# Peripherial.net
KiCad netlist of a schematic drawn in Altium Designer
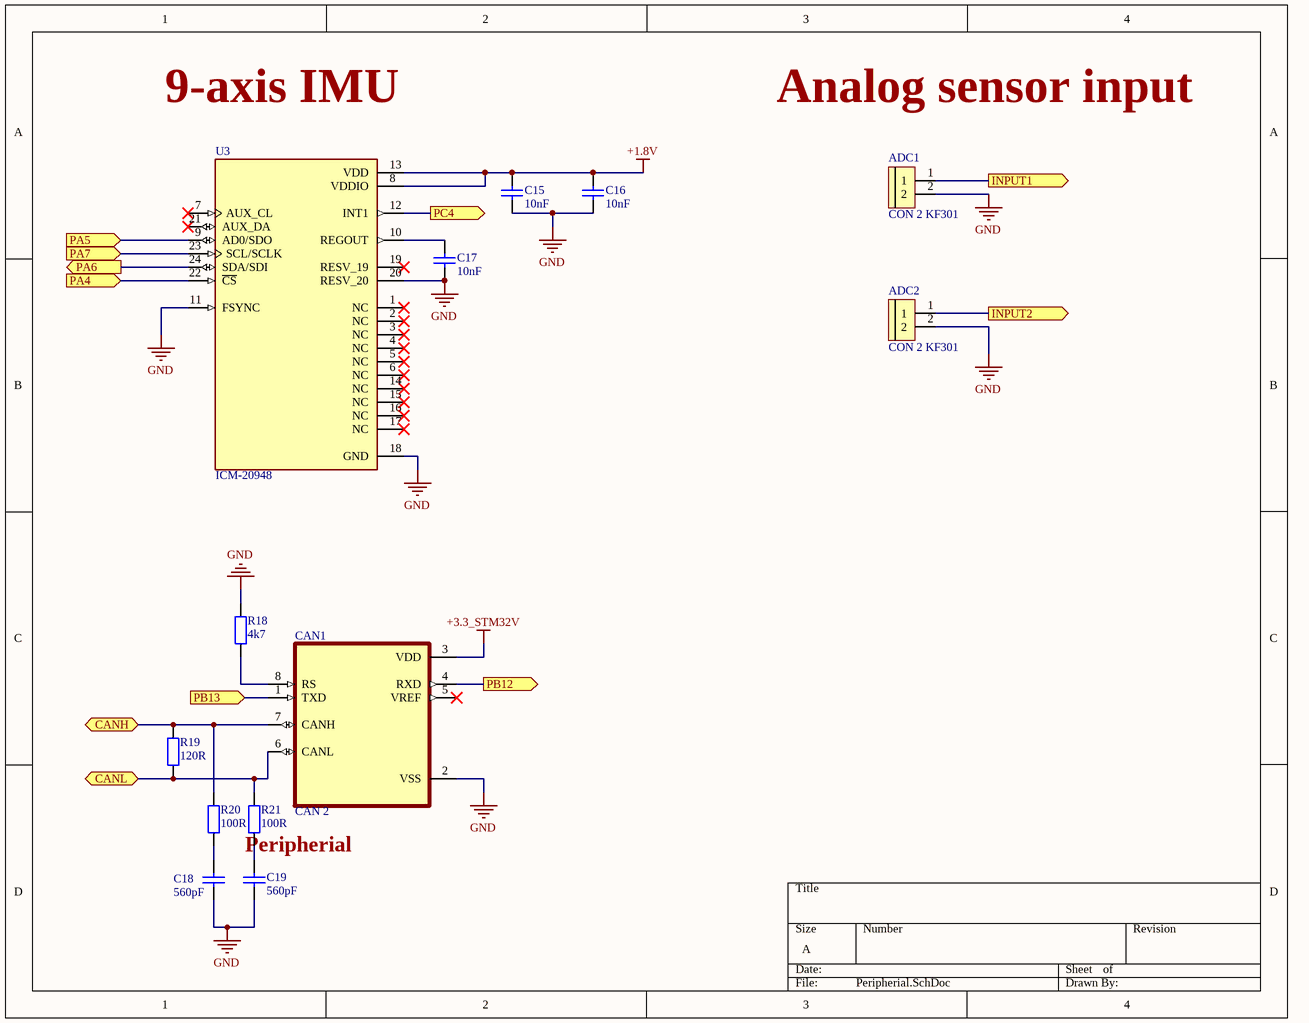
[diagram p0: Peripherial.SchDoc]

(export (version "E")
  (design (tool "Eeschema 10.0.6"))
  (components
    (comp (ref "ADC1")
      (value "CON 2 KF301")
      (footprint "Con 2 KF301 5.08")
      (description "Cắm")
      (libsource (lib "Altium_Lib_by_KhueNguyenCreator") (part "CON 2 KF301"))
    )
    (comp (ref "ADC2")
      (value "CON 2 KF301")
      (footprint "Con 2 KF301 5.08")
      (description "Cắm")
      (libsource (lib "Altium_Lib_by_KhueNguyenCreator") (part "CON 2 KF301"))
    )
    (comp (ref "C15")
      (value "10nF")
      (footprint "tu 0805")
      (description "Dán")
      (libsource (lib "Altium_Lib_by_KhueNguyenCreator") (part "Tu 0805 106 16V 10%"))
    )
    (comp (ref "C16")
      (value "10nF")
      (footprint "tu 0805")
      (description "Dán")
      (libsource (lib "Altium_Lib_by_KhueNguyenCreator") (part "Tu 0805 106 16V 10%"))
    )
    (comp (ref "C17")
      (value "10nF")
      (footprint "tu 0805")
      (description "Dán")
      (libsource (lib "Altium_Lib_by_KhueNguyenCreator") (part "Tu 0805 106 16V 10%"))
    )
    (comp (ref "C18")
      (value "560pF")
      (footprint "tu 0805")
      (description "Dán")
      (libsource (lib "Altium_Lib_by_KhueNguyenCreator") (part "Tu 0805 106 16V 10%"))
    )
    (comp (ref "C19")
      (value "560pF")
      (footprint "tu 0805")
      (description "Dán")
      (libsource (lib "Altium_Lib_by_KhueNguyenCreator") (part "Tu 0805 106 16V 10%"))
    )
    (comp (ref "CAN1")
      (value "CAN 2")
      (footprint "MCP2551-I_SN:SOIC127P599X175-8N")
      (fields
        (field (name "MF") "{'manufacturer': u'Microchip Technology'}")
        (field (name "MP") "MCP2551-I/SN")
      )
      (libsource (lib "*") (part "MCP2551-I/SN"))
    )
    (comp (ref "R18")
      (value "4k7")
      (footprint "tro smd 0805")
      (description "Dán")
      (libsource (lib "Altium_Lib_by_KhueNguyenCreator") (part "Tro 0805 1% 10k"))
    )
    (comp (ref "R19")
      (value "120R")
      (footprint "tro smd 0805")
      (description "Dán")
      (libsource (lib "Altium_Lib_by_KhueNguyenCreator") (part "Tro 0805 1% 10k"))
    )
    (comp (ref "R20")
      (value "100R")
      (footprint "tro smd 0805")
      (description "Dán")
      (libsource (lib "Altium_Lib_by_KhueNguyenCreator") (part "Tro 0805 1% 10k"))
    )
    (comp (ref "R21")
      (value "100R")
      (footprint "tro smd 0805")
      (description "Dán")
      (libsource (lib "Altium_Lib_by_KhueNguyenCreator") (part "Tro 0805 1% 10k"))
    )
    (comp (ref "U3")
      (value "ICM-20948")
      (footprint "QFN40P300X300X105-24N")
      (description "Accelerometer, Gyroscope, Magnetometer, 9 Axis Sensor IÂ²C, SPI Output")
      (libsource (lib "ICM-20948") (part "ICM-20948"))
    )
  )
  (nets
    (net (code "1") (name "+1.8V") (class "Default")
      (node (ref "C15") (pin "1") (pinfunction "1_1") (pintype "passive"))
      (node (ref "C16") (pin "1") (pinfunction "1_1") (pintype "passive"))
      (node (ref "U3") (pin "13") (pinfunction "VDD_13") (pintype "power_in"))
      (node (ref "U3") (pin "8") (pinfunction "VDDIO_8") (pintype "power_in"))
    )
    (net (code "2") (name "+3.3_STM32V") (class "Default")
      (node (ref "CAN1") (pin "3") (pinfunction "VDD_3") (pintype "power_in"))
    )
    (net (code "3") (name "/CANH") (class "Default")
      (node (ref "CAN1") (pin "7") (pinfunction "CANH_7") (pintype "bidirectional"))
      (node (ref "R19") (pin "2") (pinfunction "2_2") (pintype "passive"))
      (node (ref "R20") (pin "2") (pinfunction "2_2") (pintype "passive"))
    )
    (net (code "4") (name "/CANL") (class "Default")
      (node (ref "CAN1") (pin "6") (pinfunction "CANL_6") (pintype "bidirectional"))
      (node (ref "R19") (pin "1") (pinfunction "1_1") (pintype "passive"))
      (node (ref "R21") (pin "2") (pinfunction "2_2") (pintype "passive"))
    )
    (net (code "5") (name "/INPUT1") (class "Default")
      (node (ref "ADC1") (pin "1") (pinfunction "1_1") (pintype "passive"))
    )
    (net (code "6") (name "/INPUT2") (class "Default")
      (node (ref "ADC2") (pin "1") (pinfunction "1_1") (pintype "passive"))
    )
    (net (code "7") (name "/PA4") (class "Default")
      (node (ref "U3") (pin "22") (pinfunction "~{CS}_22") (pintype "input"))
    )
    (net (code "8") (name "/PA5") (class "Default")
      (node (ref "U3") (pin "9") (pinfunction "AD0/SDO_9") (pintype "bidirectional"))
    )
    (net (code "9") (name "/PA6") (class "Default")
      (node (ref "U3") (pin "24") (pinfunction "SDA/SDI_24") (pintype "bidirectional"))
    )
    (net (code "10") (name "/PA7") (class "Default")
      (node (ref "U3") (pin "23") (pinfunction "SCL/SCLK_23") (pintype "input"))
    )
    (net (code "11") (name "/PB12") (class "Default")
      (node (ref "CAN1") (pin "4") (pinfunction "RXD_4") (pintype "output"))
    )
    (net (code "12") (name "/PB13") (class "Default")
      (node (ref "CAN1") (pin "1") (pinfunction "TXD_1") (pintype "input"))
    )
    (net (code "13") (name "/PC4") (class "Default")
      (node (ref "U3") (pin "12") (pinfunction "INT1_12") (pintype "output"))
    )
    (net (code "14") (name "GND") (class "Default")
      (node (ref "ADC1") (pin "2") (pinfunction "2_2") (pintype "passive"))
      (node (ref "ADC2") (pin "2") (pinfunction "2_2") (pintype "passive"))
      (node (ref "C15") (pin "2") (pinfunction "2_2") (pintype "passive"))
      (node (ref "C16") (pin "2") (pinfunction "2_2") (pintype "passive"))
      (node (ref "C17") (pin "2") (pinfunction "2_2") (pintype "passive"))
      (node (ref "C18") (pin "2") (pinfunction "2_2") (pintype "passive"))
      (node (ref "C19") (pin "2") (pinfunction "2_2") (pintype "passive"))
      (node (ref "CAN1") (pin "2") (pinfunction "VSS_2") (pintype "power_in"))
      (node (ref "R18") (pin "1") (pinfunction "1_1") (pintype "passive"))
      (node (ref "U3") (pin "11") (pinfunction "FSYNC_11") (pintype "input"))
      (node (ref "U3") (pin "18") (pinfunction "GND_18") (pintype "power_in"))
      (node (ref "U3") (pin "20") (pinfunction "RESV_20_20") (pintype "passive"))
    )
    (net (code "15") (name "Net-(C18-Pad1)") (class "Default")
      (node (ref "C18") (pin "1") (pinfunction "1_1") (pintype "passive"))
      (node (ref "R20") (pin "1") (pinfunction "1_1") (pintype "passive"))
    )
    (net (code "16") (name "Net-(C19-Pad1)") (class "Default")
      (node (ref "C19") (pin "1") (pinfunction "1_1") (pintype "passive"))
      (node (ref "R21") (pin "1") (pinfunction "1_1") (pintype "passive"))
    )
    (net (code "17") (name "Net-(CAN1-RS)") (class "Default")
      (node (ref "CAN1") (pin "8") (pinfunction "RS_8") (pintype "input"))
      (node (ref "R18") (pin "2") (pinfunction "2_2") (pintype "passive"))
    )
    (net (code "18") (name "Net-(U3-REGOUT)") (class "Default")
      (node (ref "C17") (pin "1") (pinfunction "1_1") (pintype "passive"))
      (node (ref "U3") (pin "10") (pinfunction "REGOUT_10") (pintype "output"))
    )
    (net (code "19") (name "unconnected-(CAN1-VREF-Pad5)") (class "Default")
      (node (ref "CAN1") (pin "5") (pinfunction "VREF_5") (pintype "output+no_connect"))
    )
    (net (code "20") (name "unconnected-(U3-AUX_CL-Pad7)") (class "Default")
      (node (ref "U3") (pin "7") (pinfunction "AUX_CL_7") (pintype "input+no_connect"))
    )
    (net (code "21") (name "unconnected-(U3-AUX_DA-Pad21)") (class "Default")
      (node (ref "U3") (pin "21") (pinfunction "AUX_DA_21") (pintype "bidirectional+no_connect"))
    )
    (net (code "22") (name "unconnected-(U3-NC-Pad1)") (class "Default")
      (node (ref "U3") (pin "1") (pinfunction "NC_1") (pintype "passive+no_connect"))
    )
    (net (code "23") (name "unconnected-(U3-NC-Pad2)") (class "Default")
      (node (ref "U3") (pin "2") (pinfunction "NC_2") (pintype "passive+no_connect"))
    )
    (net (code "24") (name "unconnected-(U3-NC-Pad3)") (class "Default")
      (node (ref "U3") (pin "3") (pinfunction "NC_3") (pintype "passive+no_connect"))
    )
    (net (code "25") (name "unconnected-(U3-NC-Pad4)") (class "Default")
      (node (ref "U3") (pin "4") (pinfunction "NC_4") (pintype "passive+no_connect"))
    )
    (net (code "26") (name "unconnected-(U3-NC-Pad5)") (class "Default")
      (node (ref "U3") (pin "5") (pinfunction "NC_5") (pintype "passive+no_connect"))
    )
    (net (code "27") (name "unconnected-(U3-NC-Pad6)") (class "Default")
      (node (ref "U3") (pin "6") (pinfunction "NC_6") (pintype "passive+no_connect"))
    )
    (net (code "28") (name "unconnected-(U3-NC-Pad14)") (class "Default")
      (node (ref "U3") (pin "14") (pinfunction "NC_14") (pintype "passive+no_connect"))
    )
    (net (code "29") (name "unconnected-(U3-NC-Pad15)") (class "Default")
      (node (ref "U3") (pin "15") (pinfunction "NC_15") (pintype "passive+no_connect"))
    )
    (net (code "30") (name "unconnected-(U3-NC-Pad16)") (class "Default")
      (node (ref "U3") (pin "16") (pinfunction "NC_16") (pintype "passive+no_connect"))
    )
    (net (code "31") (name "unconnected-(U3-NC-Pad17)") (class "Default")
      (node (ref "U3") (pin "17") (pinfunction "NC_17") (pintype "passive+no_connect"))
    )
    (net (code "32") (name "unconnected-(U3-RESV_19-Pad19)") (class "Default")
      (node (ref "U3") (pin "19") (pinfunction "RESV_19_19") (pintype "passive+no_connect"))
    )
  )
)
